# BonekeyBonekey.net
KiCad netlist of a schematic drawn in EAGLE
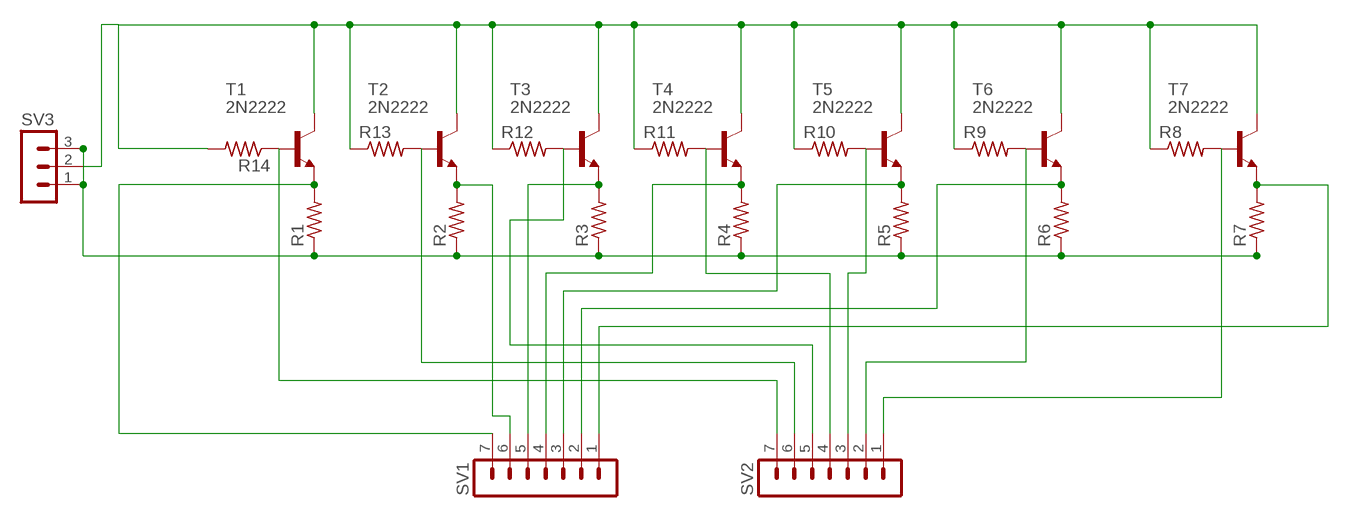
[diagram p0: schematic, sheet 1]

(export (version "E")
  (design (tool "Eeschema 10.0.6"))
  (components
    (comp (ref "R1")
      (value "R-US_0204/5")
      (footprint "eagle-import:0204_5")
      (libsource (lib "eagle-import") (part "R-US_0204/5"))
    )
    (comp (ref "R2")
      (value "R-US_0204/5")
      (footprint "eagle-import:0204_5")
      (libsource (lib "eagle-import") (part "R-US_0204/5"))
    )
    (comp (ref "R3")
      (value "R-US_0204/5")
      (footprint "eagle-import:0204_5")
      (libsource (lib "eagle-import") (part "R-US_0204/5"))
    )
    (comp (ref "R4")
      (value "R-US_0204/5")
      (footprint "eagle-import:0204_5")
      (libsource (lib "eagle-import") (part "R-US_0204/5"))
    )
    (comp (ref "R5")
      (value "R-US_0204/5")
      (footprint "eagle-import:0204_5")
      (libsource (lib "eagle-import") (part "R-US_0204/5"))
    )
    (comp (ref "R6")
      (value "R-US_0204/5")
      (footprint "eagle-import:0204_5")
      (libsource (lib "eagle-import") (part "R-US_0204/5"))
    )
    (comp (ref "R7")
      (value "R-US_0204/5")
      (footprint "eagle-import:0204_5")
      (libsource (lib "eagle-import") (part "R-US_0204/5"))
    )
    (comp (ref "R8")
      (value "R-US_0204/5")
      (footprint "eagle-import:0204_5")
      (libsource (lib "eagle-import") (part "R-US_0204/5"))
    )
    (comp (ref "R9")
      (value "R-US_0204/5")
      (footprint "eagle-import:0204_5")
      (libsource (lib "eagle-import") (part "R-US_0204/5"))
    )
    (comp (ref "R10")
      (value "R-US_0204/5")
      (footprint "eagle-import:0204_5")
      (libsource (lib "eagle-import") (part "R-US_0204/5"))
    )
    (comp (ref "R11")
      (value "R-US_0204/5")
      (footprint "eagle-import:0204_5")
      (libsource (lib "eagle-import") (part "R-US_0204/5"))
    )
    (comp (ref "R12")
      (value "R-US_0204/5")
      (footprint "eagle-import:0204_5")
      (libsource (lib "eagle-import") (part "R-US_0204/5"))
    )
    (comp (ref "R13")
      (value "R-US_0204/5")
      (footprint "eagle-import:0204_5")
      (libsource (lib "eagle-import") (part "R-US_0204/5"))
    )
    (comp (ref "R14")
      (value "R-US_0204/5")
      (footprint "eagle-import:0204_5")
      (libsource (lib "eagle-import") (part "R-US_0204/5"))
    )
    (comp (ref "SV1")
      (value "MA07-1")
      (footprint "eagle-import:MA07-1")
      (libsource (lib "eagle-import") (part "MA07-1"))
    )
    (comp (ref "SV2")
      (value "MA07-1")
      (footprint "eagle-import:MA07-1")
      (libsource (lib "eagle-import") (part "MA07-1"))
    )
    (comp (ref "SV3")
      (value "MA03-1")
      (footprint "eagle-import:MA03-1")
      (libsource (lib "eagle-import") (part "MA03-1"))
    )
    (comp (ref "T1")
      (value "2N2222")
      (footprint "eagle-import:TO18")
      (libsource (lib "eagle-import") (part "2N2222"))
    )
    (comp (ref "T2")
      (value "2N2222")
      (footprint "eagle-import:TO18")
      (libsource (lib "eagle-import") (part "2N2222"))
    )
    (comp (ref "T3")
      (value "2N2222")
      (footprint "eagle-import:TO18")
      (libsource (lib "eagle-import") (part "2N2222"))
    )
    (comp (ref "T4")
      (value "2N2222")
      (footprint "eagle-import:TO18")
      (libsource (lib "eagle-import") (part "2N2222"))
    )
    (comp (ref "T5")
      (value "2N2222")
      (footprint "eagle-import:TO18")
      (libsource (lib "eagle-import") (part "2N2222"))
    )
    (comp (ref "T6")
      (value "2N2222")
      (footprint "eagle-import:TO18")
      (libsource (lib "eagle-import") (part "2N2222"))
    )
    (comp (ref "T7")
      (value "2N2222")
      (footprint "eagle-import:TO18")
      (libsource (lib "eagle-import") (part "2N2222"))
    )
  )
  (nets
    (net (code "1") (name "Net-(R1-Pad1)") (class "Default")
      (node (ref "R1") (pin "1") (pinfunction "1_1") (pintype "passive"))
      (node (ref "R2") (pin "1") (pinfunction "1_1") (pintype "passive"))
      (node (ref "R3") (pin "1") (pinfunction "1_1") (pintype "passive"))
      (node (ref "R4") (pin "1") (pinfunction "1_1") (pintype "passive"))
      (node (ref "R5") (pin "1") (pinfunction "1_1") (pintype "passive"))
      (node (ref "R6") (pin "1") (pinfunction "1_1") (pintype "passive"))
      (node (ref "R7") (pin "1") (pinfunction "1_1") (pintype "passive"))
      (node (ref "SV3") (pin "1") (pinfunction "1_1") (pintype "passive"))
      (node (ref "SV3") (pin "3") (pinfunction "3_3") (pintype "passive"))
    )
    (net (code "2") (name "Net-(T1-B)") (class "Default")
      (node (ref "R14") (pin "1") (pinfunction "1_1") (pintype "passive"))
      (node (ref "SV2") (pin "7") (pinfunction "7_7") (pintype "passive"))
      (node (ref "T1") (pin "2") (pinfunction "B_2") (pintype "passive"))
    )
    (net (code "3") (name "Net-(T1-C)") (class "Default")
      (node (ref "R10") (pin "1") (pinfunction "1_1") (pintype "passive"))
      (node (ref "R11") (pin "1") (pinfunction "1_1") (pintype "passive"))
      (node (ref "R12") (pin "1") (pinfunction "1_1") (pintype "passive"))
      (node (ref "R13") (pin "1") (pinfunction "1_1") (pintype "passive"))
      (node (ref "R14") (pin "2") (pinfunction "2_2") (pintype "passive"))
      (node (ref "R8") (pin "1") (pinfunction "1_1") (pintype "passive"))
      (node (ref "R9") (pin "1") (pinfunction "1_1") (pintype "passive"))
      (node (ref "SV3") (pin "2") (pinfunction "2_2") (pintype "passive"))
      (node (ref "T1") (pin "3") (pinfunction "C_3") (pintype "passive"))
      (node (ref "T2") (pin "3") (pinfunction "C_3") (pintype "passive"))
      (node (ref "T3") (pin "3") (pinfunction "C_3") (pintype "passive"))
      (node (ref "T4") (pin "3") (pinfunction "C_3") (pintype "passive"))
      (node (ref "T5") (pin "3") (pinfunction "C_3") (pintype "passive"))
      (node (ref "T6") (pin "3") (pinfunction "C_3") (pintype "passive"))
      (node (ref "T7") (pin "3") (pinfunction "C_3") (pintype "passive"))
    )
    (net (code "4") (name "Net-(T1-E)") (class "Default")
      (node (ref "R1") (pin "2") (pinfunction "2_2") (pintype "passive"))
      (node (ref "SV1") (pin "7") (pinfunction "7_7") (pintype "passive"))
      (node (ref "T1") (pin "1") (pinfunction "E_1") (pintype "passive"))
    )
    (net (code "5") (name "Net-(T2-B)") (class "Default")
      (node (ref "R13") (pin "2") (pinfunction "2_2") (pintype "passive"))
      (node (ref "SV2") (pin "6") (pinfunction "6_6") (pintype "passive"))
      (node (ref "T2") (pin "2") (pinfunction "B_2") (pintype "passive"))
    )
    (net (code "6") (name "Net-(T2-E)") (class "Default")
      (node (ref "R2") (pin "2") (pinfunction "2_2") (pintype "passive"))
      (node (ref "SV1") (pin "6") (pinfunction "6_6") (pintype "passive"))
      (node (ref "T2") (pin "1") (pinfunction "E_1") (pintype "passive"))
    )
    (net (code "7") (name "Net-(T3-B)") (class "Default")
      (node (ref "R12") (pin "2") (pinfunction "2_2") (pintype "passive"))
      (node (ref "SV2") (pin "5") (pinfunction "5_5") (pintype "passive"))
      (node (ref "T3") (pin "2") (pinfunction "B_2") (pintype "passive"))
    )
    (net (code "8") (name "Net-(T3-E)") (class "Default")
      (node (ref "R3") (pin "2") (pinfunction "2_2") (pintype "passive"))
      (node (ref "SV1") (pin "5") (pinfunction "5_5") (pintype "passive"))
      (node (ref "T3") (pin "1") (pinfunction "E_1") (pintype "passive"))
    )
    (net (code "9") (name "Net-(T4-B)") (class "Default")
      (node (ref "R11") (pin "2") (pinfunction "2_2") (pintype "passive"))
      (node (ref "SV2") (pin "4") (pinfunction "4_4") (pintype "passive"))
      (node (ref "T4") (pin "2") (pinfunction "B_2") (pintype "passive"))
    )
    (net (code "10") (name "Net-(T4-E)") (class "Default")
      (node (ref "R4") (pin "2") (pinfunction "2_2") (pintype "passive"))
      (node (ref "SV1") (pin "4") (pinfunction "4_4") (pintype "passive"))
      (node (ref "T4") (pin "1") (pinfunction "E_1") (pintype "passive"))
    )
    (net (code "11") (name "Net-(T5-B)") (class "Default")
      (node (ref "R10") (pin "2") (pinfunction "2_2") (pintype "passive"))
      (node (ref "SV2") (pin "3") (pinfunction "3_3") (pintype "passive"))
      (node (ref "T5") (pin "2") (pinfunction "B_2") (pintype "passive"))
    )
    (net (code "12") (name "Net-(T5-E)") (class "Default")
      (node (ref "R5") (pin "2") (pinfunction "2_2") (pintype "passive"))
      (node (ref "SV1") (pin "3") (pinfunction "3_3") (pintype "passive"))
      (node (ref "T5") (pin "1") (pinfunction "E_1") (pintype "passive"))
    )
    (net (code "13") (name "Net-(T6-B)") (class "Default")
      (node (ref "R9") (pin "2") (pinfunction "2_2") (pintype "passive"))
      (node (ref "SV2") (pin "2") (pinfunction "2_2") (pintype "passive"))
      (node (ref "T6") (pin "2") (pinfunction "B_2") (pintype "passive"))
    )
    (net (code "14") (name "Net-(T6-E)") (class "Default")
      (node (ref "R6") (pin "2") (pinfunction "2_2") (pintype "passive"))
      (node (ref "SV1") (pin "2") (pinfunction "2_2") (pintype "passive"))
      (node (ref "T6") (pin "1") (pinfunction "E_1") (pintype "passive"))
    )
    (net (code "15") (name "Net-(T7-B)") (class "Default")
      (node (ref "R8") (pin "2") (pinfunction "2_2") (pintype "passive"))
      (node (ref "SV2") (pin "1") (pinfunction "1_1") (pintype "passive"))
      (node (ref "T7") (pin "2") (pinfunction "B_2") (pintype "passive"))
    )
    (net (code "16") (name "Net-(T7-E)") (class "Default")
      (node (ref "R7") (pin "2") (pinfunction "2_2") (pintype "passive"))
      (node (ref "SV1") (pin "1") (pinfunction "1_1") (pintype "passive"))
      (node (ref "T7") (pin "1") (pinfunction "E_1") (pintype "passive"))
    )
  )
)
